# 5v_3v3_vr.net
KiCad netlist of a schematic drawn in Altium Designer
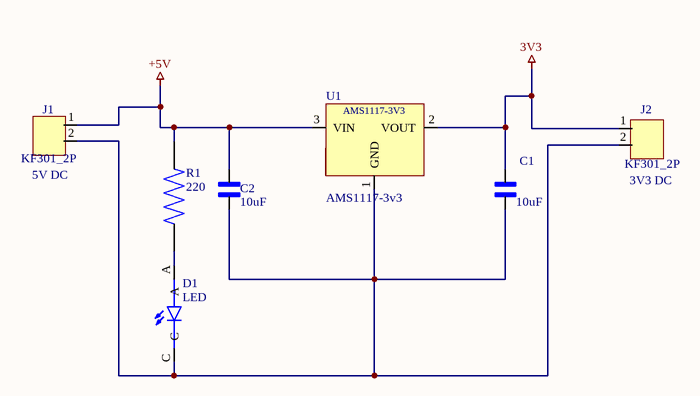
[diagram p0: 5v_3v3_vr.SchDoc]

(export (version "E")
  (design (tool "Eeschema 10.0.6"))
  (components
    (comp (ref "C1")
      (value "10uF")
      (footprint "CAPC2012X94N")
      (description "10000 pF Â±5% 16V Ceramic Capacitor X7R 0805 (2012 Metric)")
      (fields (field (name "MF") "AVX") (field (name "MP") "0805YC103J4T2A"))
      (libsource (lib "0805YC103J4T2A") (part "0805YC103J4T2A"))
    )
    (comp (ref "C2")
      (value "10uF")
      (footprint "CAPC2012X94N")
      (description "10000 pF Â±5% 16V Ceramic Capacitor X7R 0805 (2012 Metric)")
      (fields (field (name "MF") "AVX") (field (name "MP") "0805YC103J4T2A"))
      (libsource (lib "0805YC103J4T2A") (part "0805YC103J4T2A"))
    )
    (comp (ref "D1")
      (value "LED")
      (footprint "LED_WP7113ID")
      (description "Red 617nm LED Indication - Discrete 2V Radial")
      (fields (field (name "MP") "WP7113ID") (field (name "MF") "Kingbright"))
      (libsource (lib "WP7113ID") (part "WP7113ID"))
    )
    (comp (ref "J1")
      (value "KF301_2P")
      (footprint "KF301_2P")
      (libsource (lib "User_Library") (part "KF301_2P"))
    )
    (comp (ref "J2") (value "KF301_2P") (footprint "KF301_2P") (libsource (lib "") (part "KF301_2P_1")))
    (comp (ref "R1")
      (value "220")
      (footprint "RESC2012X60N")
      (description "910 Ohms Â±1% 0.125W, 1/8W Chip Resistor 0805 (2012 Metric) Moisture Resistant Thick Film")
      (fields (field (name "MF") "Yageo") (field (name "MP") "RC0805FR-07910RL"))
      (libsource (lib "RC0805FR-07910RL") (part "RC0805FR-07910RL"))
    )
    (comp (ref "U1")
      (value "AMS1117-3v3")
      (footprint "AMS1117-3V3")
      (libsource (lib "User_Library") (part "AMS1117-3v3"))
    )
  )
  (nets
    (net (code "1") (name "+5V") (class "Default")
      (node (ref "C2") (pin "2") (pinfunction "2_2") (pintype "passive"))
      (node (ref "J1") (pin "1") (pintype "passive"))
      (node (ref "R1") (pin "1") (pinfunction "1_1") (pintype "passive"))
      (node (ref "U1") (pin "3") (pinfunction "VIN_3") (pintype "power_in"))
    )
    (net (code "2") (name "3V3") (class "Default")
      (node (ref "C1") (pin "2") (pinfunction "2_2") (pintype "passive"))
      (node (ref "J2") (pin "1") (pintype "passive"))
      (node (ref "U1") (pin "2") (pinfunction "VOUT_2") (pintype "power_in"))
    )
    (net (code "3") (name "Net-(D1-PadA)") (class "Default")
      (node (ref "D1") (pin "A") (pinfunction "A_A") (pintype "passive"))
      (node (ref "R1") (pin "2") (pinfunction "2_2") (pintype "passive"))
    )
    (net (code "4") (name "Net-(U1-GND)") (class "Default")
      (node (ref "C1") (pin "1") (pinfunction "1_1") (pintype "passive"))
      (node (ref "C2") (pin "1") (pinfunction "1_1") (pintype "passive"))
      (node (ref "D1") (pin "C") (pinfunction "C_C") (pintype "passive"))
      (node (ref "J1") (pin "2") (pintype "passive"))
      (node (ref "J2") (pin "2") (pintype "passive"))
      (node (ref "U1") (pin "1") (pinfunction "GND_1") (pintype "power_in"))
    )
  )
)
